# micro2.net
KiCad netlist of a schematic drawn in EAGLE
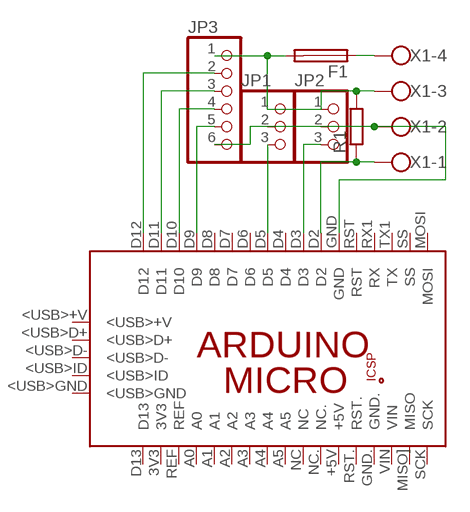
[diagram p0: schematic, sheet 1]

(export (version "E")
  (design (tool "Eeschema 10.0.6"))
  (components
    (comp (ref "F1")
      (value "GSH15")
      (footprint "eagle-import:GSH15")
      (fields (field (name "MPN") "64900001039"))
      (libsource (lib "eagle-import") (part "GSH15"))
    )
    (comp (ref "JP1")
      (value "PINHD-1X3")
      (footprint "eagle-import:1X03")
      (libsource (lib "eagle-import") (part "PINHD-1X3"))
    )
    (comp (ref "JP2")
      (value "PINHD-1X3")
      (footprint "eagle-import:1X03")
      (libsource (lib "eagle-import") (part "PINHD-1X3"))
    )
    (comp (ref "JP3")
      (value "PINHD-1X6")
      (footprint "eagle-import:1X06")
      (libsource (lib "eagle-import") (part "PINHD-1X6"))
    )
    (comp (ref "PCB1")
      (value "ARDUINO_MICRO")
      (footprint "eagle-import:ARDUINO_MICRO")
      (libsource (lib "eagle-import") (part "ARDUINO_MICRO"))
    )
    (comp (ref "R1")
      (value "R-EU_0207/10")
      (footprint "eagle-import:0207_10")
      (libsource (lib "eagle-import") (part "R-EU_0207/10"))
    )
    (comp (ref "X1")
      (value "W237-4")
      (footprint "eagle-import:W237-4")
      (libsource (lib "eagle-import") (part "W237-4"))
    )
  )
  (nets
    (net (code "1") (name "Net-(JP1-Pad3)") (class "Default")
      (node (ref "JP1") (pin "3") (pinfunction "3_3") (pintype "passive"))
      (node (ref "PCB1") (pin "D5") (pinfunction "D5_D5") (pintype "bidirectional"))
    )
    (net (code "2") (name "Net-(JP2-Pad3)") (class "Default")
      (node (ref "JP2") (pin "3") (pinfunction "3_3") (pintype "passive"))
      (node (ref "PCB1") (pin "D3") (pinfunction "D3_D3") (pintype "bidirectional"))
    )
    (net (code "3") (name "Net-(JP3-Pad2)") (class "Default")
      (node (ref "JP3") (pin "2") (pinfunction "2_2") (pintype "passive"))
      (node (ref "PCB1") (pin "D12") (pinfunction "D12_D12") (pintype "bidirectional"))
    )
    (net (code "4") (name "Net-(JP3-Pad3)") (class "Default")
      (node (ref "JP3") (pin "3") (pinfunction "3_3") (pintype "passive"))
      (node (ref "PCB1") (pin "D11") (pinfunction "D11_D11") (pintype "bidirectional"))
    )
    (net (code "5") (name "Net-(JP3-Pad4)") (class "Default")
      (node (ref "JP3") (pin "4") (pinfunction "4_4") (pintype "passive"))
      (node (ref "PCB1") (pin "D10") (pinfunction "D10_D10") (pintype "bidirectional"))
    )
    (net (code "6") (name "Net-(JP3-Pad5)") (class "Default")
      (node (ref "JP3") (pin "5") (pinfunction "5_5") (pintype "passive"))
      (node (ref "PCB1") (pin "D9") (pinfunction "D9_D9") (pintype "bidirectional"))
    )
    (net (code "7") (name "Net-(X1A-KL)") (class "Default")
      (node (ref "PCB1") (pin "D2") (pinfunction "D2_D2") (pintype "bidirectional"))
      (node (ref "R1") (pin "1") (pinfunction "1_1") (pintype "passive"))
      (node (ref "X1") (pin "1") (pinfunction "KL_1") (pintype "passive"))
    )
    (net (code "8") (name "Net-(X1B-KL)") (class "Default")
      (node (ref "JP1") (pin "2") (pinfunction "2_2") (pintype "passive"))
      (node (ref "JP2") (pin "2") (pinfunction "2_2") (pintype "passive"))
      (node (ref "JP3") (pin "6") (pinfunction "6_6") (pintype "passive"))
      (node (ref "PCB1") (pin "GND") (pinfunction "GND_GND") (pintype "bidirectional"))
      (node (ref "X1") (pin "2") (pinfunction "KL_2") (pintype "passive"))
    )
    (net (code "9") (name "Net-(X1C-KL)") (class "Default")
      (node (ref "F1") (pin "2") (pinfunction "2_2") (pintype "passive"))
      (node (ref "JP1") (pin "1") (pinfunction "1_1") (pintype "passive"))
      (node (ref "JP2") (pin "1") (pinfunction "1_1") (pintype "passive"))
      (node (ref "JP3") (pin "1") (pinfunction "1_1") (pintype "passive"))
      (node (ref "R1") (pin "2") (pinfunction "2_2") (pintype "passive"))
      (node (ref "X1") (pin "3") (pinfunction "KL_3") (pintype "passive"))
    )
    (net (code "10") (name "Net-(X1D-KL)") (class "Default")
      (node (ref "F1") (pin "1") (pinfunction "1_1") (pintype "passive"))
      (node (ref "X1") (pin "4") (pinfunction "KL_4") (pintype "passive"))
    )
    (net (code "11") (name "unconnected-(PCB1-MISO-PadMISO])") (class "Default")
      (node (ref "PCB1") (pin "MISO]") (pinfunction "MISO_MISO]") (pintype "bidirectional"))
    )
    (net (code "12") (name "unconnected-(PCB1-Pad+5V)") (class "Default")
      (node (ref "PCB1") (pin "+5V") (pinfunction "+5V_+5V") (pintype "bidirectional"))
    )
    (net (code "13") (name "unconnected-(PCB1-Pad3V3)") (class "Default")
      (node (ref "PCB1") (pin "3V3") (pinfunction "3V3_3V3") (pintype "bidirectional"))
    )
    (net (code "14") (name "unconnected-(PCB1-Pad5V)") (class "Default")
      (node (ref "PCB1") (pin "5V") (pinfunction "5V_5V") (pintype "bidirectional"))
    )
    (net (code "15") (name "unconnected-(PCB1-Pad<USB>+V)") (class "Default")
      (node (ref "PCB1") (pin "<USB>+V") (pinfunction "<USB>+V_<USB>+V") (pintype "bidirectional"))
    )
    (net (code "16") (name "unconnected-(PCB1-Pad<USB>D+)") (class "Default")
      (node (ref "PCB1") (pin "<USB>D+") (pinfunction "<USB>D+_<USB>D+") (pintype "bidirectional"))
    )
    (net (code "17") (name "unconnected-(PCB1-Pad<USB>D-)") (class "Default")
      (node (ref "PCB1") (pin "<USB>D-") (pinfunction "<USB>D-_<USB>D-") (pintype "bidirectional"))
    )
    (net (code "18") (name "unconnected-(PCB1-Pad<USB>GND)") (class "Default")
      (node (ref "PCB1") (pin "<USB>GND") (pinfunction "<USB>GND_<USB>GND") (pintype "bidirectional"))
    )
    (net (code "19") (name "unconnected-(PCB1-Pad<USB>ID)") (class "Default")
      (node (ref "PCB1") (pin "<USB>ID") (pinfunction "<USB>ID_<USB>ID") (pintype "bidirectional"))
    )
    (net (code "20") (name "unconnected-(PCB1-PadA0)") (class "Default")
      (node (ref "PCB1") (pin "A0") (pinfunction "A0_A0") (pintype "bidirectional"))
    )
    (net (code "21") (name "unconnected-(PCB1-PadA1)") (class "Default")
      (node (ref "PCB1") (pin "A1") (pinfunction "A1_A1") (pintype "bidirectional"))
    )
    (net (code "22") (name "unconnected-(PCB1-PadA2)") (class "Default")
      (node (ref "PCB1") (pin "A2") (pinfunction "A2_A2") (pintype "bidirectional"))
    )
    (net (code "23") (name "unconnected-(PCB1-PadA3)") (class "Default")
      (node (ref "PCB1") (pin "A3") (pinfunction "A3_A3") (pintype "bidirectional"))
    )
    (net (code "24") (name "unconnected-(PCB1-PadA4)") (class "Default")
      (node (ref "PCB1") (pin "A4") (pinfunction "A4_A4") (pintype "bidirectional"))
    )
    (net (code "25") (name "unconnected-(PCB1-PadA5)") (class "Default")
      (node (ref "PCB1") (pin "A5") (pinfunction "A5_A5") (pintype "bidirectional"))
    )
    (net (code "26") (name "unconnected-(PCB1-PadD4)") (class "Default")
      (node (ref "PCB1") (pin "D4") (pinfunction "D4_D4") (pintype "bidirectional"))
    )
    (net (code "27") (name "unconnected-(PCB1-PadD6)") (class "Default")
      (node (ref "PCB1") (pin "D6") (pinfunction "D6_D6") (pintype "bidirectional"))
    )
    (net (code "28") (name "unconnected-(PCB1-PadD7)") (class "Default")
      (node (ref "PCB1") (pin "D7") (pinfunction "D7_D7") (pintype "bidirectional"))
    )
    (net (code "29") (name "unconnected-(PCB1-PadD8)") (class "Default")
      (node (ref "PCB1") (pin "D8") (pinfunction "D8_D8") (pintype "bidirectional"))
    )
    (net (code "30") (name "unconnected-(PCB1-PadD13)") (class "Default")
      (node (ref "PCB1") (pin "D13") (pinfunction "D13_D13") (pintype "bidirectional"))
    )
    (net (code "31") (name "unconnected-(PCB1-PadGND.)") (class "Default")
      (node (ref "PCB1") (pin "GND.") (pinfunction "GND._GND.") (pintype "bidirectional"))
    )
    (net (code "32") (name "unconnected-(PCB1-PadGND_)") (class "Default")
      (node (ref "PCB1") (pin "GND_") (pinfunction "GND__GND_") (pintype "bidirectional"))
    )
    (net (code "33") (name "unconnected-(PCB1-PadMISO.)") (class "Default")
      (node (ref "PCB1") (pin "MISO.") (pinfunction "MISO._MISO.") (pintype "bidirectional"))
    )
    (net (code "34") (name "unconnected-(PCB1-PadMOSI)") (class "Default")
      (node (ref "PCB1") (pin "MOSI") (pinfunction "MOSI_MOSI") (pintype "bidirectional"))
    )
    (net (code "35") (name "unconnected-(PCB1-PadMOSI.)") (class "Default")
      (node (ref "PCB1") (pin "MOSI.") (pinfunction "MOSI._MOSI.") (pintype "bidirectional"))
    )
    (net (code "36") (name "unconnected-(PCB1-PadNC)") (class "Default")
      (node (ref "PCB1") (pin "NC") (pinfunction "NC_NC") (pintype "bidirectional"))
    )
    (net (code "37") (name "unconnected-(PCB1-PadNC.)") (class "Default")
      (node (ref "PCB1") (pin "NC.") (pinfunction "NC._NC.") (pintype "bidirectional"))
    )
    (net (code "38") (name "unconnected-(PCB1-PadREF)") (class "Default")
      (node (ref "PCB1") (pin "REF") (pinfunction "REF_REF") (pintype "bidirectional"))
    )
    (net (code "39") (name "unconnected-(PCB1-PadRESET..)") (class "Default")
      (node (ref "PCB1") (pin "RESET..") (pinfunction "RESET.._RESET..") (pintype "bidirectional"))
    )
    (net (code "40") (name "unconnected-(PCB1-PadRST)") (class "Default")
      (node (ref "PCB1") (pin "RST") (pinfunction "RST_RST") (pintype "bidirectional"))
    )
    (net (code "41") (name "unconnected-(PCB1-PadRST.)") (class "Default")
      (node (ref "PCB1") (pin "RST.") (pinfunction "RST._RST.") (pintype "bidirectional"))
    )
    (net (code "42") (name "unconnected-(PCB1-PadSCK)") (class "Default")
      (node (ref "PCB1") (pin "SCK") (pinfunction "SCK_SCK") (pintype "bidirectional"))
    )
    (net (code "43") (name "unconnected-(PCB1-PadSCK.)") (class "Default")
      (node (ref "PCB1") (pin "SCK.") (pinfunction "SCK._SCK.") (pintype "bidirectional"))
    )
    (net (code "44") (name "unconnected-(PCB1-PadSS)") (class "Default")
      (node (ref "PCB1") (pin "SS") (pinfunction "SS_SS") (pintype "bidirectional"))
    )
    (net (code "45") (name "unconnected-(PCB1-PadVIN)") (class "Default")
      (node (ref "PCB1") (pin "VIN") (pinfunction "VIN_VIN") (pintype "bidirectional"))
    )
    (net (code "46") (name "unconnected-(PCB1-RX-PadRX1)") (class "Default")
      (node (ref "PCB1") (pin "RX1") (pinfunction "RX_RX1") (pintype "bidirectional"))
    )
    (net (code "47") (name "unconnected-(PCB1-TX-PadTX1)") (class "Default")
      (node (ref "PCB1") (pin "TX1") (pinfunction "TX_TX1") (pintype "bidirectional"))
    )
  )
)
